# V4-AddOnZigbee-DIL-V02-004.net
KiCad netlist of a schematic drawn in EAGLE
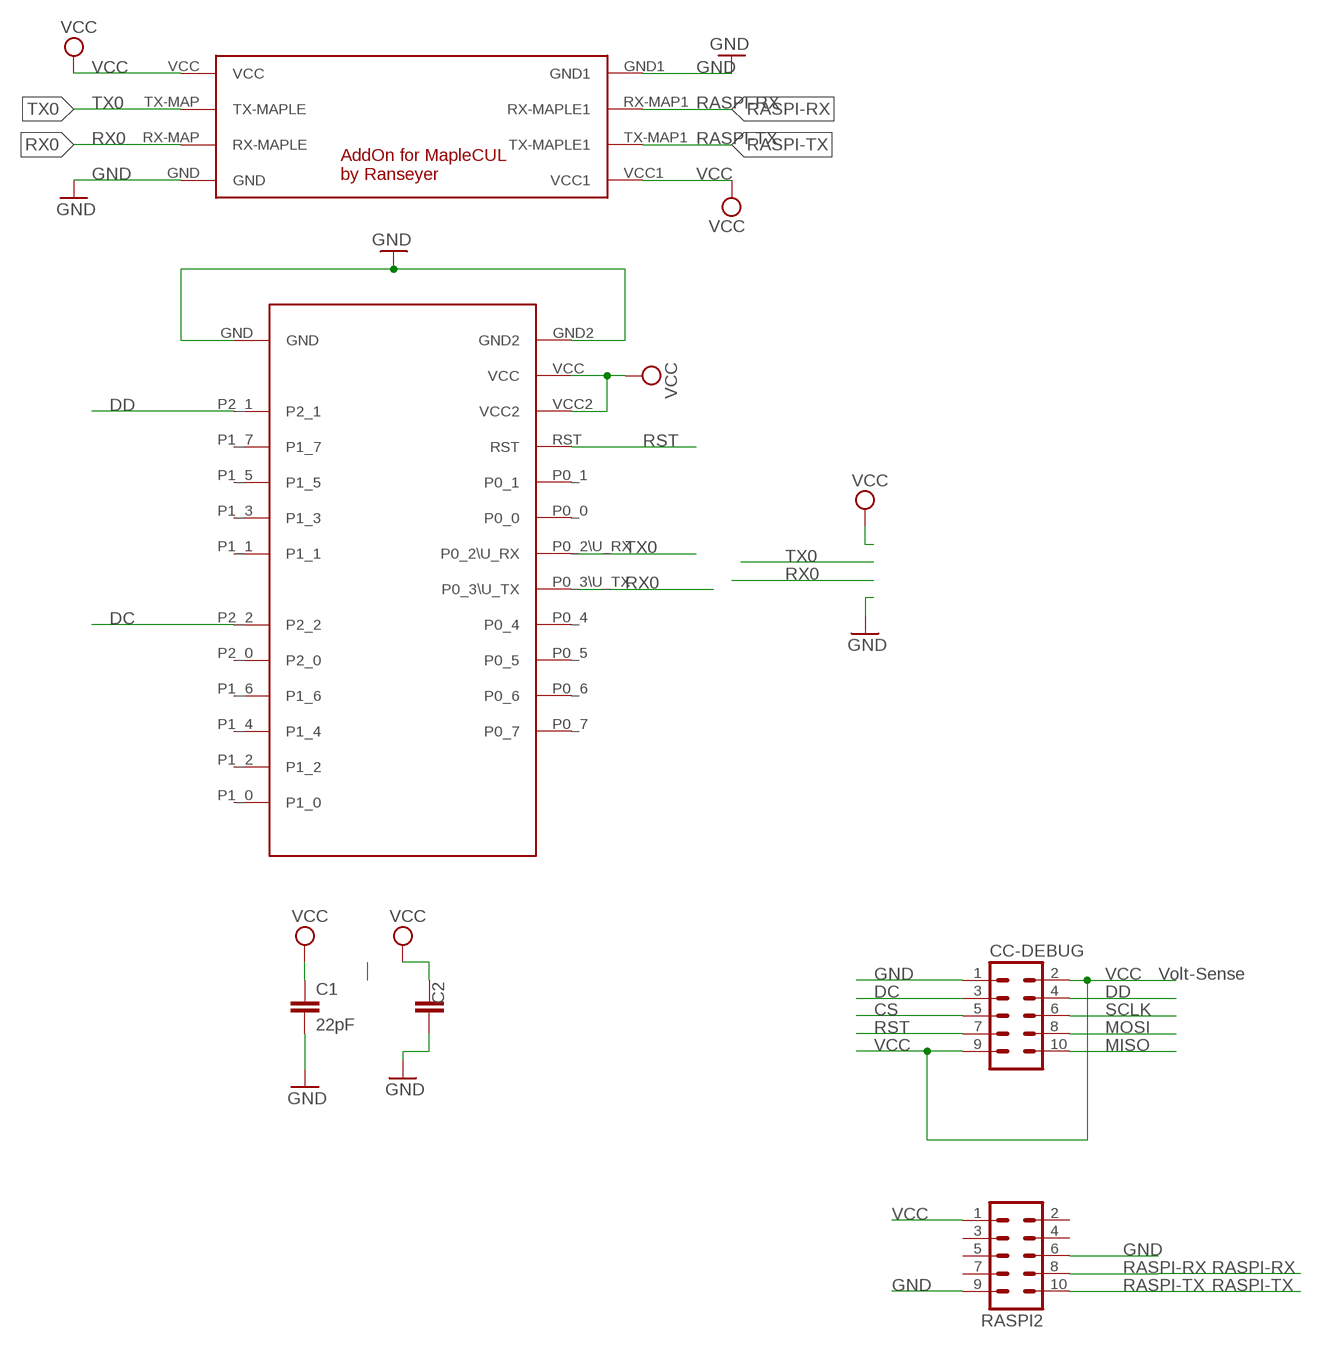
[diagram p0: schematic, sheet 1]

(export (version "E")
  (design (tool "Eeschema 10.0.6"))
  (components
    (comp (ref "C1")
      (value "22pF")
      (footprint "eagle-import:C0805")
      (libsource (lib "eagle-import") (part "C-EUC0805"))
    )
    (comp (ref "C2")
      (value "C-EUC1812")
      (footprint "eagle-import:C1812")
      (libsource (lib "eagle-import") (part "C-EUC1812"))
    )
    (comp (ref "CC-DEBUG")
      (value "CONN_05X2SHD_LOCK")
      (footprint "eagle-import:2X5-SHROUDED_LOCK")
      (libsource (lib "eagle-import") (part "CONN_05X2SHD_LOCK"))
    )
    (comp (ref "RASPI2")
      (value "MA05-2")
      (footprint "eagle-import:MA05-2")
      (libsource (lib "eagle-import") (part "MA05-2"))
    )
    (comp (ref "U$1")
      (value "MAPLE-CUL-ADDON-V01")
      (footprint "eagle-import:MAPLE-CUL-V01")
      (libsource (lib "eagle-import") (part "MAPLE-CUL-ADDON-V01"))
    )
    (comp (ref "U$3")
      (value "CC2530_MODULE")
      (footprint "eagle-import:CC2530_DIL")
      (libsource (lib "eagle-import") (part "CC2530_MODULE"))
    )
  )
  (nets
    (net (code "1") (name "/CS") (class "Default")
      (node (ref "CC-DEBUG") (pin "5") (pinfunction "5_5") (pintype "passive"))
    )
    (net (code "2") (name "/DC") (class "Default")
      (node (ref "CC-DEBUG") (pin "3") (pinfunction "3_3") (pintype "passive"))
      (node (ref "U$3") (pin "P2_2") (pinfunction "P2_2_P2_2") (pintype "bidirectional"))
    )
    (net (code "3") (name "/DD") (class "Default")
      (node (ref "CC-DEBUG") (pin "4") (pinfunction "4_4") (pintype "passive"))
      (node (ref "U$3") (pin "P2_1") (pinfunction "P2_1_P2_1") (pintype "bidirectional"))
    )
    (net (code "4") (name "/MISO") (class "Default")
      (node (ref "CC-DEBUG") (pin "10") (pinfunction "10_10") (pintype "passive"))
    )
    (net (code "5") (name "/MOSI") (class "Default")
      (node (ref "CC-DEBUG") (pin "8") (pinfunction "8_8") (pintype "passive"))
    )
    (net (code "6") (name "/RST") (class "Default")
      (node (ref "CC-DEBUG") (pin "7") (pinfunction "7_7") (pintype "passive"))
      (node (ref "U$3") (pin "RST") (pinfunction "RST_RST") (pintype "bidirectional"))
    )
    (net (code "7") (name "/SCLK") (class "Default")
      (node (ref "CC-DEBUG") (pin "6") (pinfunction "6_6") (pintype "passive"))
    )
    (net (code "8") (name "GND") (class "Default")
      (node (ref "C1") (pin "2") (pinfunction "2_2") (pintype "passive"))
      (node (ref "C2") (pin "1") (pinfunction "1_1") (pintype "passive"))
      (node (ref "CC-DEBUG") (pin "1") (pinfunction "1_1") (pintype "passive"))
      (node (ref "RASPI2") (pin "6") (pinfunction "6_6") (pintype "passive"))
      (node (ref "RASPI2") (pin "9") (pinfunction "9_9") (pintype "passive"))
      (node (ref "U$1") (pin "GND") (pinfunction "GND_GND") (pintype "bidirectional"))
      (node (ref "U$1") (pin "GND1") (pinfunction "GND1_GND1") (pintype "bidirectional"))
      (node (ref "U$3") (pin "GND") (pinfunction "GND_GND") (pintype "bidirectional"))
      (node (ref "U$3") (pin "GND2") (pinfunction "GND2_GND2") (pintype "bidirectional"))
    )
    (net (code "9") (name "RASPI-RX") (class "Default")
      (node (ref "RASPI2") (pin "8") (pinfunction "8_8") (pintype "passive"))
      (node (ref "U$1") (pin "RX-MAP1") (pinfunction "RX-MAPLE1_RX-MAP1") (pintype "bidirectional"))
    )
    (net (code "10") (name "RASPI-TX") (class "Default")
      (node (ref "RASPI2") (pin "10") (pinfunction "10_10") (pintype "passive"))
      (node (ref "U$1") (pin "TX-MAP1") (pinfunction "TX-MAPLE1_TX-MAP1") (pintype "bidirectional"))
    )
    (net (code "11") (name "RX0") (class "Default")
      (node (ref "U$1") (pin "RX-MAP") (pinfunction "RX-MAPLE_RX-MAP") (pintype "bidirectional"))
      (node (ref "U$3") (pin "P0_3\\U_TX") (pinfunction "P0_3\\U_TX_P0_3\\U_TX") (pintype "bidirectional"))
    )
    (net (code "12") (name "TX0") (class "Default")
      (node (ref "U$1") (pin "TX-MAP") (pinfunction "TX-MAPLE_TX-MAP") (pintype "bidirectional"))
      (node (ref "U$3") (pin "P0_2\\U_RX") (pinfunction "P0_2\\U_RX_P0_2\\U_RX") (pintype "bidirectional"))
    )
    (net (code "13") (name "VCC") (class "Default")
      (node (ref "C1") (pin "1") (pinfunction "1_1") (pintype "passive"))
      (node (ref "C2") (pin "2") (pinfunction "2_2") (pintype "passive"))
      (node (ref "CC-DEBUG") (pin "2") (pinfunction "2_2") (pintype "passive"))
      (node (ref "CC-DEBUG") (pin "9") (pinfunction "9_9") (pintype "passive"))
      (node (ref "RASPI2") (pin "1") (pinfunction "1_1") (pintype "passive"))
      (node (ref "U$1") (pin "VCC") (pinfunction "VCC_VCC") (pintype "bidirectional"))
      (node (ref "U$1") (pin "VCC1") (pinfunction "VCC1_VCC1") (pintype "bidirectional"))
      (node (ref "U$3") (pin "VCC") (pinfunction "VCC_VCC") (pintype "bidirectional"))
      (node (ref "U$3") (pin "VCC2") (pinfunction "VCC2_VCC2") (pintype "bidirectional"))
    )
    (net (code "14") (name "unconnected-(RASPI2-Pad2)") (class "Default")
      (node (ref "RASPI2") (pin "2") (pinfunction "2_2") (pintype "passive"))
    )
    (net (code "15") (name "unconnected-(RASPI2-Pad3)") (class "Default")
      (node (ref "RASPI2") (pin "3") (pinfunction "3_3") (pintype "passive"))
    )
    (net (code "16") (name "unconnected-(RASPI2-Pad4)") (class "Default")
      (node (ref "RASPI2") (pin "4") (pinfunction "4_4") (pintype "passive"))
    )
    (net (code "17") (name "unconnected-(RASPI2-Pad5)") (class "Default")
      (node (ref "RASPI2") (pin "5") (pinfunction "5_5") (pintype "passive"))
    )
    (net (code "18") (name "unconnected-(RASPI2-Pad7)") (class "Default")
      (node (ref "RASPI2") (pin "7") (pinfunction "7_7") (pintype "passive"))
    )
    (net (code "19") (name "unconnected-(U$3-PadP0_0)") (class "Default")
      (node (ref "U$3") (pin "P0_0") (pinfunction "P0_0_P0_0") (pintype "bidirectional"))
    )
    (net (code "20") (name "unconnected-(U$3-PadP0_1)") (class "Default")
      (node (ref "U$3") (pin "P0_1") (pinfunction "P0_1_P0_1") (pintype "bidirectional"))
    )
    (net (code "21") (name "unconnected-(U$3-PadP0_4)") (class "Default")
      (node (ref "U$3") (pin "P0_4") (pinfunction "P0_4_P0_4") (pintype "bidirectional"))
    )
    (net (code "22") (name "unconnected-(U$3-PadP0_5)") (class "Default")
      (node (ref "U$3") (pin "P0_5") (pinfunction "P0_5_P0_5") (pintype "bidirectional"))
    )
    (net (code "23") (name "unconnected-(U$3-PadP0_6)") (class "Default")
      (node (ref "U$3") (pin "P0_6") (pinfunction "P0_6_P0_6") (pintype "bidirectional"))
    )
    (net (code "24") (name "unconnected-(U$3-PadP0_7)") (class "Default")
      (node (ref "U$3") (pin "P0_7") (pinfunction "P0_7_P0_7") (pintype "bidirectional"))
    )
    (net (code "25") (name "unconnected-(U$3-PadP1_0)") (class "Default")
      (node (ref "U$3") (pin "P1_0") (pinfunction "P1_0_P1_0") (pintype "bidirectional"))
    )
    (net (code "26") (name "unconnected-(U$3-PadP1_1)") (class "Default")
      (node (ref "U$3") (pin "P1_1") (pinfunction "P1_1_P1_1") (pintype "bidirectional"))
    )
    (net (code "27") (name "unconnected-(U$3-PadP1_2)") (class "Default")
      (node (ref "U$3") (pin "P1_2") (pinfunction "P1_2_P1_2") (pintype "bidirectional"))
    )
    (net (code "28") (name "unconnected-(U$3-PadP1_3)") (class "Default")
      (node (ref "U$3") (pin "P1_3") (pinfunction "P1_3_P1_3") (pintype "bidirectional"))
    )
    (net (code "29") (name "unconnected-(U$3-PadP1_4)") (class "Default")
      (node (ref "U$3") (pin "P1_4") (pinfunction "P1_4_P1_4") (pintype "bidirectional"))
    )
    (net (code "30") (name "unconnected-(U$3-PadP1_5)") (class "Default")
      (node (ref "U$3") (pin "P1_5") (pinfunction "P1_5_P1_5") (pintype "bidirectional"))
    )
    (net (code "31") (name "unconnected-(U$3-PadP1_6)") (class "Default")
      (node (ref "U$3") (pin "P1_6") (pinfunction "P1_6_P1_6") (pintype "bidirectional"))
    )
    (net (code "32") (name "unconnected-(U$3-PadP1_7)") (class "Default")
      (node (ref "U$3") (pin "P1_7") (pinfunction "P1_7_P1_7") (pintype "bidirectional"))
    )
    (net (code "33") (name "unconnected-(U$3-PadP2_0)") (class "Default")
      (node (ref "U$3") (pin "P2_0") (pinfunction "P2_0_P2_0") (pintype "bidirectional"))
    )
  )
)
